# DM1092_LEVEL_SHIFT.net
KiCad netlist of a schematic drawn in Altium Designer
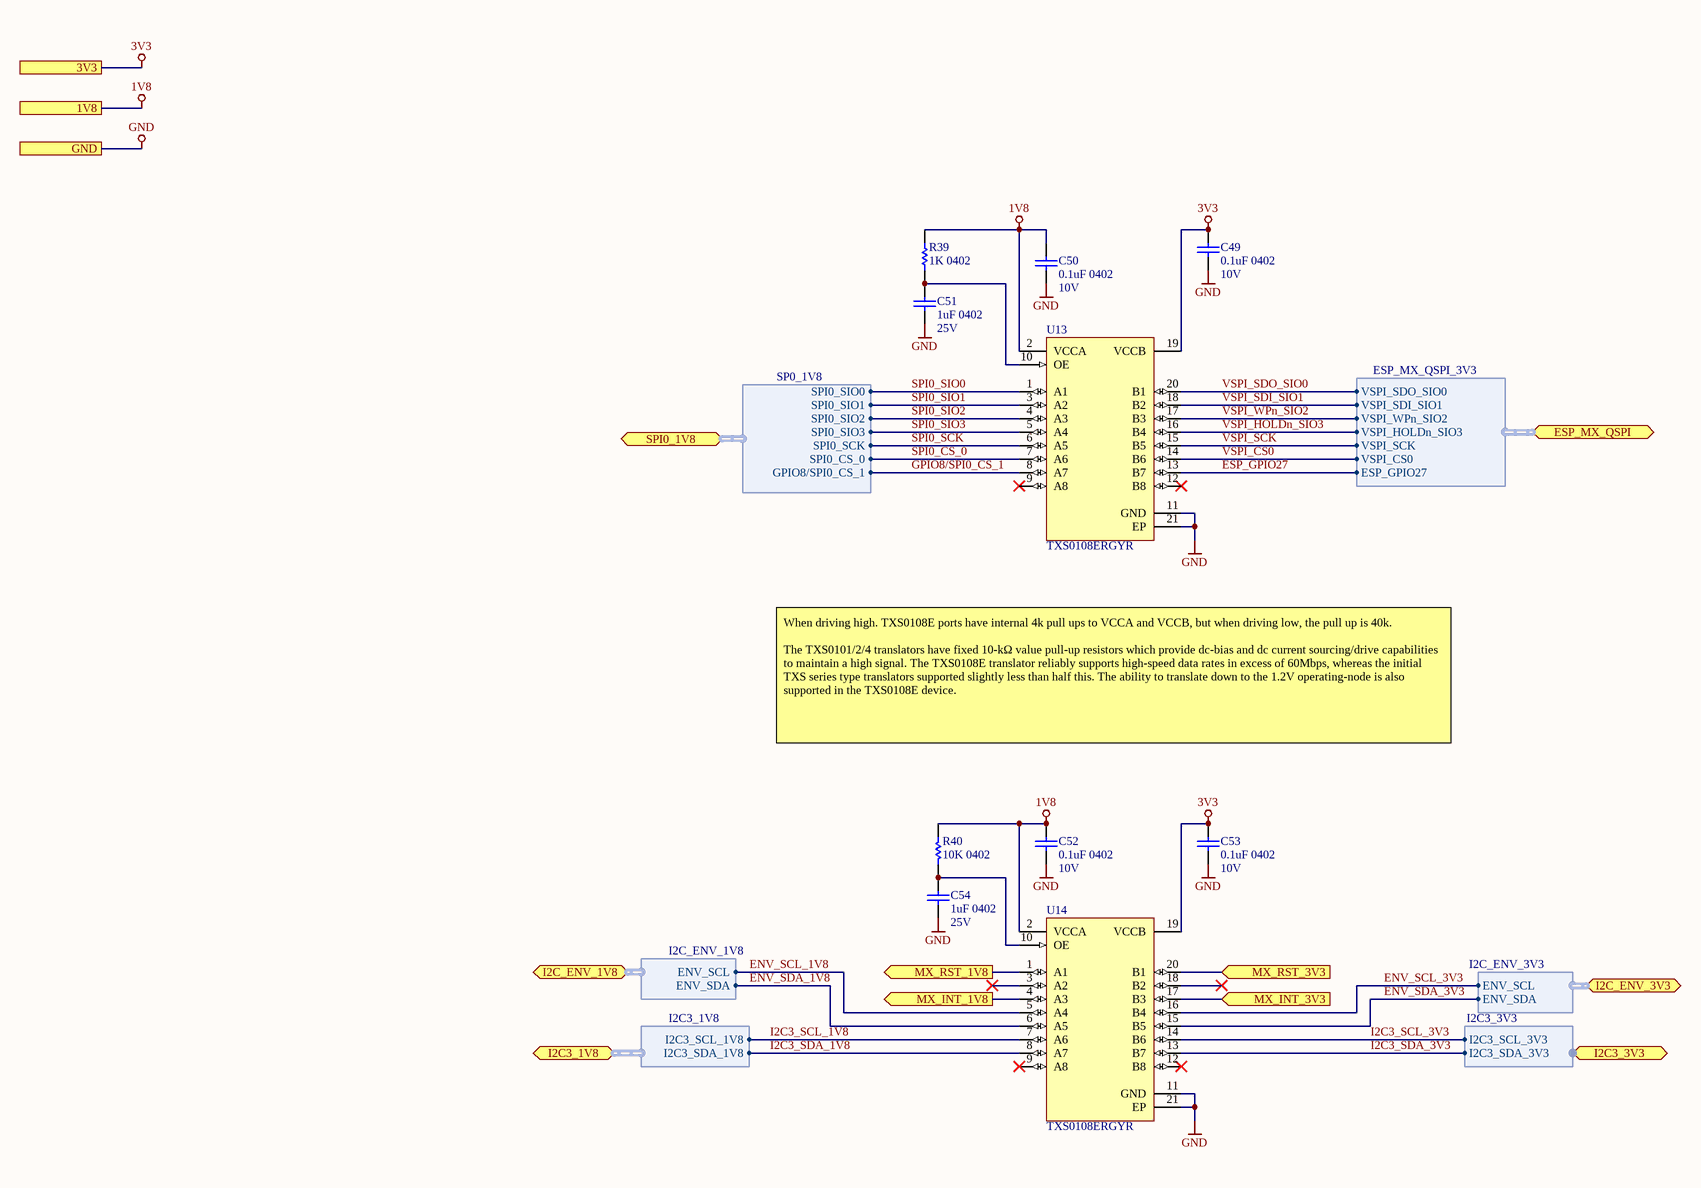
[diagram p0: DM1092_LEVEL_SHIFT.SchDoc]

(export (version "E")
  (design (tool "Eeschema 10.0.6"))
  (components
    (comp (ref "C49")
      (value "0.1uF 0402")
      (footprint "CAP_Altium_Vault_Generic:CAPC0402(1005)70_N")
      (description "CAP CER 0.1UF 10V X7R 0402 5%")
      (fields (field (name "TOLERANCE") "5%") (field (name "VOLTAGE RATING") "10V"))
      (libsource (lib "LuxonisMaster") (part "GRM155R71A104JA01D"))
    )
    (comp (ref "C50")
      (value "0.1uF 0402")
      (footprint "CAP_Altium_Vault_Generic:CAPC0402(1005)70_N")
      (description "CAP CER 0.1UF 10V X7R 0402 5%")
      (fields (field (name "TOLERANCE") "5%") (field (name "VOLTAGE RATING") "10V"))
      (libsource (lib "LuxonisMaster") (part "GRM155R71A104JA01D"))
    )
    (comp (ref "C51")
      (value "1uF 0402")
      (footprint "CAP_Altium_Vault_Generic:CAPC0402(1005)70_N")
      (description "CAP CER 1UF 25V X5R 0402 10%")
      (fields
        (field (name "TOLERANCE") "10%")
        (field (name "VOLTAGE") "25V")
        (field (name "VOLTAGE RATING") "25V")
      )
      (libsource (lib "LuxonisMaster") (part "GRM155R61E105KA12D"))
    )
    (comp (ref "C52")
      (value "0.1uF 0402")
      (footprint "CAP_Altium_Vault_Generic:CAPC0402(1005)70_N")
      (description "CAP CER 0.1UF 10V X7R 0402 5%")
      (fields (field (name "TOLERANCE") "5%") (field (name "VOLTAGE RATING") "10V"))
      (libsource (lib "LuxonisMaster") (part "GRM155R71A104JA01D"))
    )
    (comp (ref "C53")
      (value "0.1uF 0402")
      (footprint "CAP_Altium_Vault_Generic:CAPC0402(1005)70_N")
      (description "CAP CER 0.1UF 10V X7R 0402 5%")
      (fields (field (name "TOLERANCE") "5%") (field (name "VOLTAGE RATING") "10V"))
      (libsource (lib "LuxonisMaster") (part "GRM155R71A104JA01D"))
    )
    (comp (ref "C54")
      (value "1uF 0402")
      (footprint "CAP_Altium_Vault_Generic:CAPC0402(1005)70_N")
      (description "CAP CER 1UF 25V X5R 0402 10%")
      (fields
        (field (name "TOLERANCE") "10%")
        (field (name "VOLTAGE") "25V")
        (field (name "VOLTAGE RATING") "25V")
      )
      (libsource (lib "LuxonisMaster") (part "GRM155R61E105KA12D"))
    )
    (comp (ref "R39")
      (value "1K 0402")
      (footprint "RES_Altium_Vault_Generic:RESC0402(1005)_N")
      (fields (field (name "TOLERANCE") "1%"))
      (libsource (lib "LuxonisMaster") (part "RC0402FR-071KL"))
    )
    (comp (ref "R40")
      (value "10K 0402")
      (footprint "RES_Altium_Vault_Generic:RESC0402(1005)_N")
      (fields (field (name "TOLERANCE") "1%"))
      (libsource (lib "LuxonisMaster") (part "RC0402FR-1310KL"))
    )
    (comp (ref "U13")
      (value "TXS0108ERGYR")
      (footprint "LuxonisMaster:TXS0108ERGYR")
      (description "IC TRNSLTR BIDIRECTIONAL 20VQFN")
      (libsource (lib "LuxonisMaster") (part "TXS0108ERGYR"))
    )
    (comp (ref "U14")
      (value "TXS0108ERGYR")
      (footprint "LuxonisMaster:TXS0108ERGYR")
      (description "IC TRNSLTR BIDIRECTIONAL 20VQFN")
      (libsource (lib "LuxonisMaster") (part "TXS0108ERGYR"))
    )
  )
  (nets
    (net (code "7") (name "/ENV_SCL_1V8") (class "Default")
      (node (ref "U14") (pin "5") (pinfunction "A4_5") (pintype "bidirectional"))
    )
    (net (code "8") (name "/ENV_SCL_3V3") (class "Default")
      (node (ref "U14") (pin "16") (pinfunction "B4_16") (pintype "bidirectional"))
    )
    (net (code "9") (name "/ENV_SDA_1V8") (class "Default")
      (node (ref "U14") (pin "6") (pinfunction "A5_6") (pintype "bidirectional"))
    )
    (net (code "10") (name "/ENV_SDA_3V3") (class "Default")
      (node (ref "U14") (pin "15") (pinfunction "B5_15") (pintype "bidirectional"))
    )
    (net (code "11") (name "/ESP_GPIO27") (class "Default")
      (node (ref "U13") (pin "13") (pinfunction "B7_13") (pintype "bidirectional"))
    )
    (net (code "12") (name "/GPIO8{slash}SPI0_CS_1") (class "Default")
      (node (ref "U13") (pin "8") (pinfunction "A7_8") (pintype "bidirectional"))
    )
    (net (code "13") (name "/I2C3_SCL_1V8") (class "Default")
      (node (ref "U14") (pin "7") (pinfunction "A6_7") (pintype "bidirectional"))
    )
    (net (code "14") (name "/I2C3_SCL_3V3") (class "Default")
      (node (ref "U14") (pin "14") (pinfunction "B6_14") (pintype "bidirectional"))
    )
    (net (code "15") (name "/I2C3_SDA_1V8") (class "Default")
      (node (ref "U14") (pin "8") (pinfunction "A7_8") (pintype "bidirectional"))
    )
    (net (code "16") (name "/I2C3_SDA_3V3") (class "Default")
      (node (ref "U14") (pin "13") (pinfunction "B7_13") (pintype "bidirectional"))
    )
    (net (code "17") (name "/MX_INT_1V8") (class "Default")
      (node (ref "U14") (pin "4") (pinfunction "A3_4") (pintype "bidirectional"))
    )
    (net (code "18") (name "/MX_INT_3V3") (class "Default")
      (node (ref "U14") (pin "17") (pinfunction "B3_17") (pintype "bidirectional"))
    )
    (net (code "19") (name "/MX_RST_1V8") (class "Default")
      (node (ref "U14") (pin "1") (pinfunction "A1_1") (pintype "bidirectional"))
    )
    (net (code "20") (name "/MX_RST_3V3") (class "Default")
      (node (ref "U14") (pin "20") (pinfunction "B1_20") (pintype "bidirectional"))
    )
    (net (code "21") (name "/SPI0_CS_0") (class "Default")
      (node (ref "U13") (pin "7") (pinfunction "A6_7") (pintype "bidirectional"))
    )
    (net (code "22") (name "/SPI0_SCK") (class "Default")
      (node (ref "U13") (pin "6") (pinfunction "A5_6") (pintype "bidirectional"))
    )
    (net (code "23") (name "/SPI0_SIO0") (class "Default")
      (node (ref "U13") (pin "1") (pinfunction "A1_1") (pintype "bidirectional"))
    )
    (net (code "24") (name "/SPI0_SIO1") (class "Default")
      (node (ref "U13") (pin "3") (pinfunction "A2_3") (pintype "bidirectional"))
    )
    (net (code "25") (name "/SPI0_SIO2") (class "Default")
      (node (ref "U13") (pin "4") (pinfunction "A3_4") (pintype "bidirectional"))
    )
    (net (code "26") (name "/SPI0_SIO3") (class "Default")
      (node (ref "U13") (pin "5") (pinfunction "A4_5") (pintype "bidirectional"))
    )
    (net (code "27") (name "/VSPI_CS0") (class "Default")
      (node (ref "U13") (pin "14") (pinfunction "B6_14") (pintype "bidirectional"))
    )
    (net (code "28") (name "/VSPI_HOLDn_SIO3") (class "Default")
      (node (ref "U13") (pin "16") (pinfunction "B4_16") (pintype "bidirectional"))
    )
    (net (code "29") (name "/VSPI_SCK") (class "Default")
      (node (ref "U13") (pin "15") (pinfunction "B5_15") (pintype "bidirectional"))
    )
    (net (code "30") (name "/VSPI_SDI_SIO1") (class "Default")
      (node (ref "U13") (pin "18") (pinfunction "B2_18") (pintype "bidirectional"))
    )
    (net (code "31") (name "/VSPI_SDO_SIO0") (class "Default")
      (node (ref "U13") (pin "20") (pinfunction "B1_20") (pintype "bidirectional"))
    )
    (net (code "32") (name "/VSPI_WPn_SIO2") (class "Default")
      (node (ref "U13") (pin "17") (pinfunction "B3_17") (pintype "bidirectional"))
    )
    (net (code "39") (name "1V8") (class "Default")
      (node (ref "C50") (pin "2") (pinfunction "2_2") (pintype "passive"))
      (node (ref "C52") (pin "2") (pinfunction "2_2") (pintype "passive"))
      (node (ref "R39") (pin "2") (pinfunction "2_2") (pintype "passive"))
      (node (ref "R40") (pin "1") (pinfunction "1_1") (pintype "passive"))
      (node (ref "U13") (pin "2") (pinfunction "VCCA_2") (pintype "power_in"))
      (node (ref "U14") (pin "2") (pinfunction "VCCA_2") (pintype "power_in"))
    )
    (net (code "40") (name "3V3") (class "Default")
      (node (ref "C49") (pin "2") (pinfunction "2_2") (pintype "passive"))
      (node (ref "C53") (pin "2") (pinfunction "2_2") (pintype "passive"))
      (node (ref "U13") (pin "19") (pinfunction "VCCB_19") (pintype "power_in"))
      (node (ref "U14") (pin "19") (pinfunction "VCCB_19") (pintype "power_in"))
    )
    (net (code "41") (name "GND") (class "Default")
      (node (ref "C49") (pin "1") (pinfunction "1_1") (pintype "passive"))
      (node (ref "C50") (pin "1") (pinfunction "1_1") (pintype "passive"))
      (node (ref "C51") (pin "1") (pinfunction "1_1") (pintype "passive"))
      (node (ref "C52") (pin "1") (pinfunction "1_1") (pintype "passive"))
      (node (ref "C53") (pin "1") (pinfunction "1_1") (pintype "passive"))
      (node (ref "C54") (pin "1") (pinfunction "1_1") (pintype "passive"))
      (node (ref "U13") (pin "11") (pinfunction "GND_11") (pintype "power_in"))
      (node (ref "U13") (pin "21") (pinfunction "EP_21") (pintype "power_in"))
      (node (ref "U14") (pin "11") (pinfunction "GND_11") (pintype "power_in"))
      (node (ref "U14") (pin "21") (pinfunction "EP_21") (pintype "power_in"))
    )
    (net (code "42") (name "Net-(U13-OE)") (class "Default")
      (node (ref "C51") (pin "2") (pinfunction "2_2") (pintype "passive"))
      (node (ref "R39") (pin "1") (pinfunction "1_1") (pintype "passive"))
      (node (ref "U13") (pin "10") (pinfunction "OE_10") (pintype "input"))
    )
    (net (code "43") (name "Net-(U14-OE)") (class "Default")
      (node (ref "C54") (pin "2") (pinfunction "2_2") (pintype "passive"))
      (node (ref "R40") (pin "2") (pinfunction "2_2") (pintype "passive"))
      (node (ref "U14") (pin "10") (pinfunction "OE_10") (pintype "input"))
    )
    (net (code "44") (name "unconnected-(U13-A8-Pad9)") (class "Default")
      (node (ref "U13") (pin "9") (pinfunction "A8_9") (pintype "bidirectional+no_connect"))
    )
    (net (code "45") (name "unconnected-(U13-B8-Pad12)") (class "Default")
      (node (ref "U13") (pin "12") (pinfunction "B8_12") (pintype "bidirectional+no_connect"))
    )
    (net (code "46") (name "unconnected-(U14-A2-Pad3)") (class "Default")
      (node (ref "U14") (pin "3") (pinfunction "A2_3") (pintype "bidirectional+no_connect"))
    )
    (net (code "47") (name "unconnected-(U14-A8-Pad9)") (class "Default")
      (node (ref "U14") (pin "9") (pinfunction "A8_9") (pintype "bidirectional+no_connect"))
    )
    (net (code "48") (name "unconnected-(U14-B2-Pad18)") (class "Default")
      (node (ref "U14") (pin "18") (pinfunction "B2_18") (pintype "bidirectional+no_connect"))
    )
    (net (code "49") (name "unconnected-(U14-B8-Pad12)") (class "Default")
      (node (ref "U14") (pin "12") (pinfunction "B8_12") (pintype "bidirectional+no_connect"))
    )
  )
)
